# power-supply_combined_v1.net
KiCad netlist of a schematic drawn in EAGLE
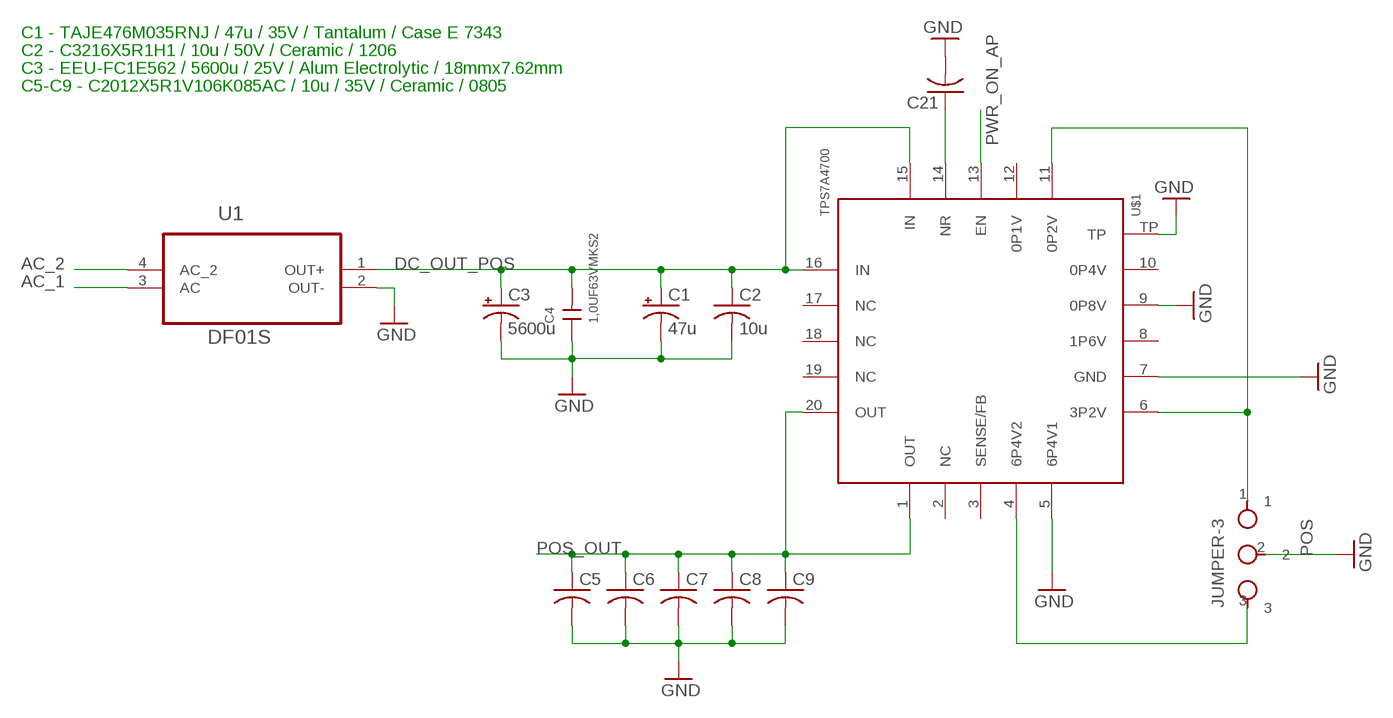
[diagram p0: schematic, sheet 1]
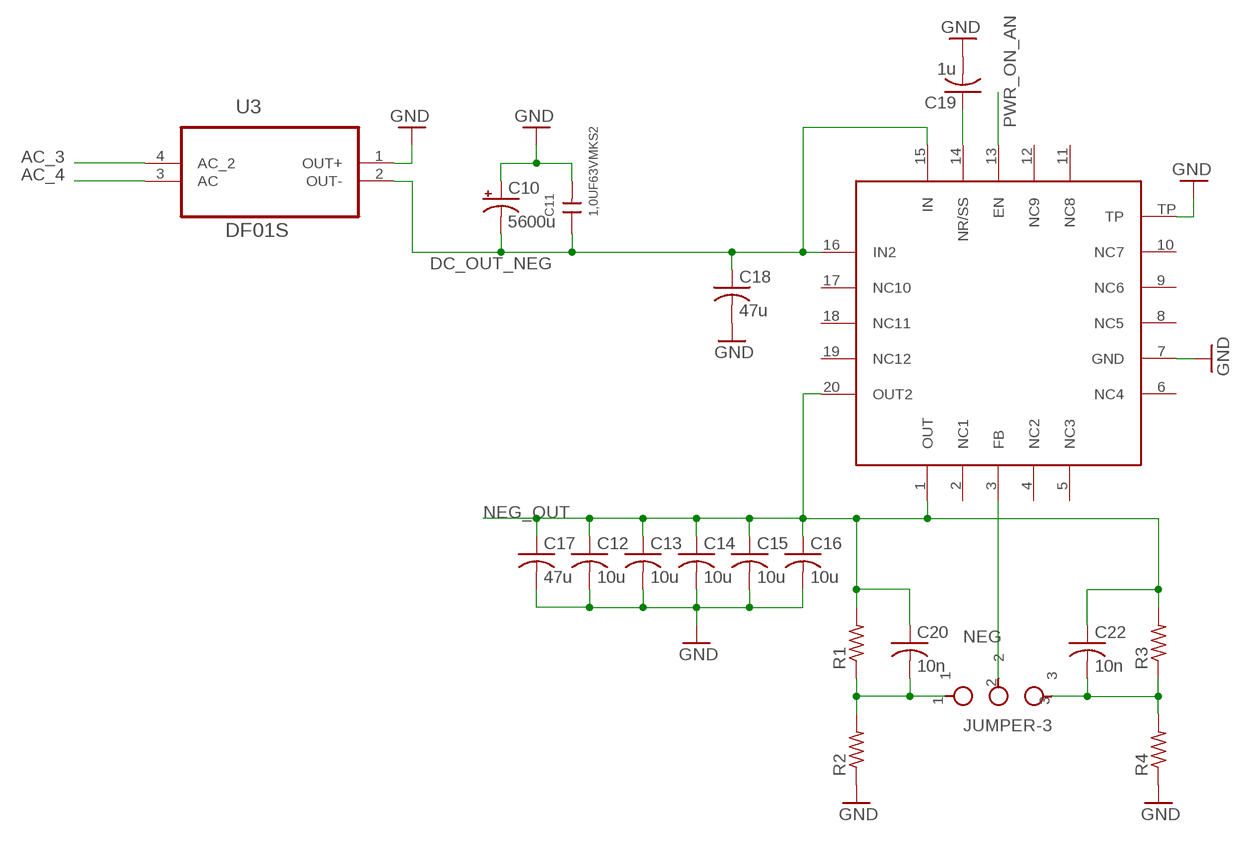
[diagram p1: schematic, sheet 2]
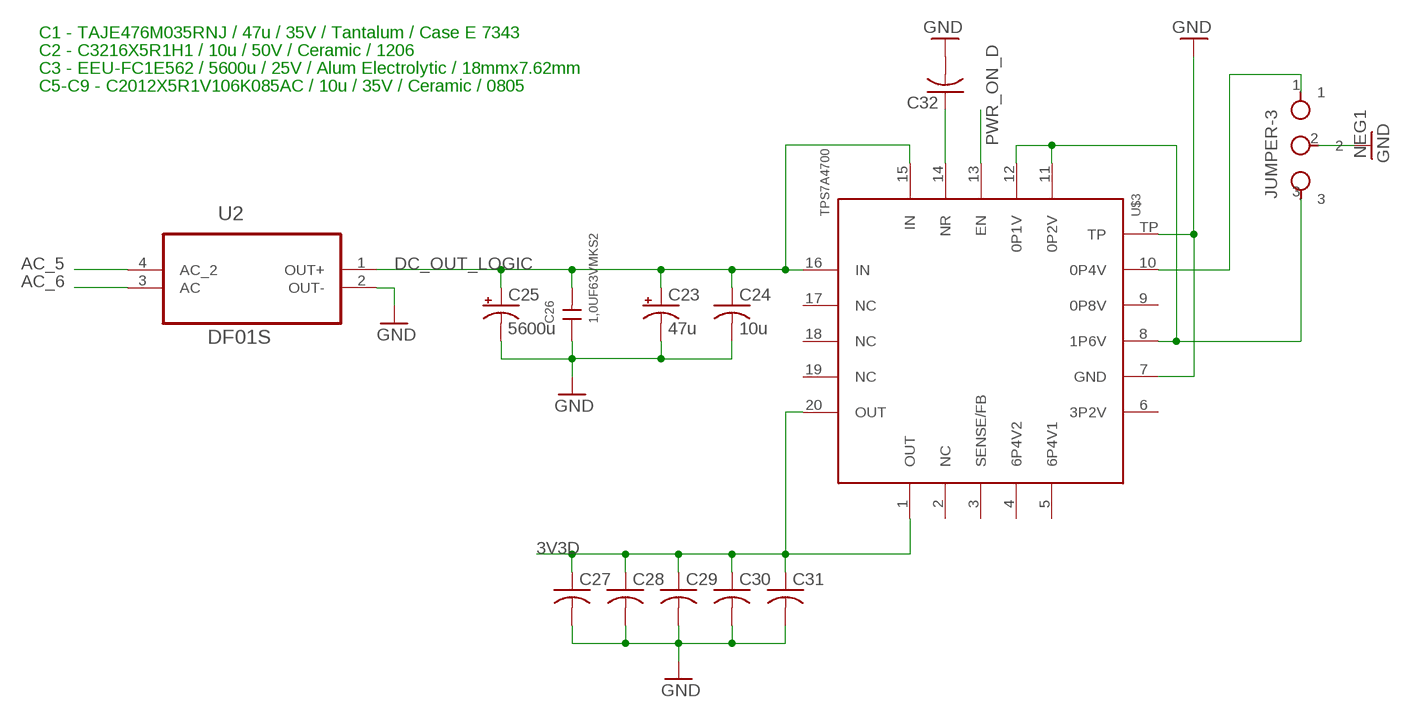
[diagram p2: schematic, sheet 3]
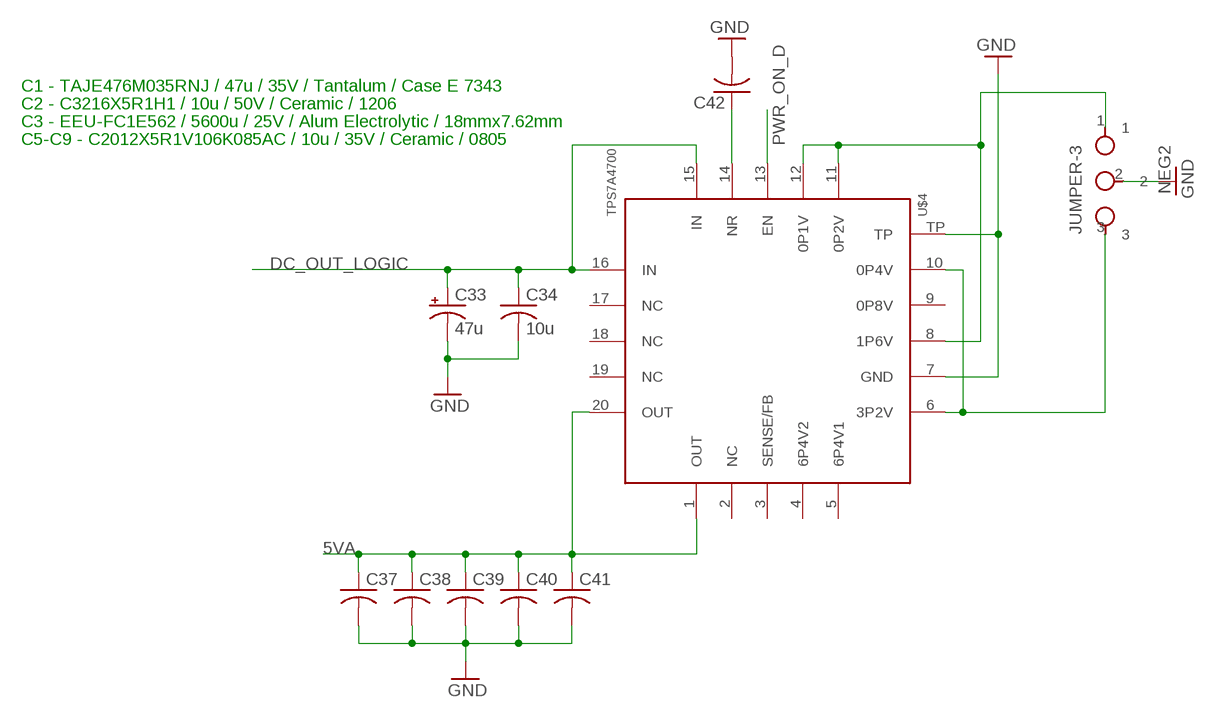
[diagram p3: schematic, sheet 4]
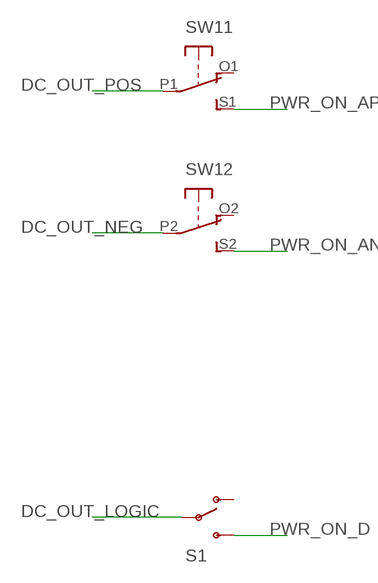
[diagram p4: schematic, sheet 5]

(export (version "E")
  (design (tool "Eeschema 10.0.6"))
  (components
    (comp (ref "S1")
      (value "SWITCH-SPDTSMD")
      (footprint "eagle-import:AYZ0202")
      (libsource (lib "eagle-import") (part "SWITCH-SPDTSMD"))
    )
    (comp (ref "SW1")
      (value "DPDT-EG1390")
      (footprint "eagle-import:EG1390")
      (libsource (lib "eagle-import") (part "DPDT-EG1390"))
    )
    (comp (ref "C33")
      (value "47u")
      (footprint "eagle-import:SMC_E")
      (libsource (lib "eagle-import") (part "CPOL-USSMCE"))
    )
    (comp (ref "C34")
      (value "10u")
      (footprint "eagle-import:C1206")
      (libsource (lib "eagle-import") (part "C-USC1206"))
    )
    (comp (ref "C37")
      (value "C-USC0805")
      (footprint "eagle-import:C0805")
      (libsource (lib "eagle-import") (part "C-USC0805"))
    )
    (comp (ref "C38")
      (value "C-USC0805")
      (footprint "eagle-import:C0805")
      (libsource (lib "eagle-import") (part "C-USC0805"))
    )
    (comp (ref "C39")
      (value "C-USC0805")
      (footprint "eagle-import:C0805")
      (libsource (lib "eagle-import") (part "C-USC0805"))
    )
    (comp (ref "C40")
      (value "C-USC0805")
      (footprint "eagle-import:C0805")
      (libsource (lib "eagle-import") (part "C-USC0805"))
    )
    (comp (ref "C41")
      (value "C-USC0805")
      (footprint "eagle-import:C0805")
      (libsource (lib "eagle-import") (part "C-USC0805"))
    )
    (comp (ref "C42")
      (value "C-USC0603")
      (footprint "eagle-import:C0603")
      (libsource (lib "eagle-import") (part "C-USC0603"))
    )
    (comp (ref "NEG2")
      (value "JUMPER-3")
      (footprint "eagle-import:1X03")
      (libsource (lib "eagle-import") (part "JUMPER-3"))
    )
    (comp (ref "U$4")
      (value "TPS7A4700")
      (footprint "eagle-import:VQFN-20")
      (libsource (lib "eagle-import") (part "TPS7A4700"))
    )
    (comp (ref "C23")
      (value "47u")
      (footprint "eagle-import:SMC_E")
      (libsource (lib "eagle-import") (part "CPOL-USSMCE"))
    )
    (comp (ref "C24")
      (value "10u")
      (footprint "eagle-import:C1206")
      (libsource (lib "eagle-import") (part "C-USC1206"))
    )
    (comp (ref "C25")
      (value "5600u")
      (footprint "eagle-import:E7,5-18")
      (libsource (lib "eagle-import") (part "CPOL-USE7.5-18"))
    )
    (comp (ref "C26")
      (value "1,0UF63VMKS2")
      (footprint "eagle-import:5,0X10,0RM5,0")
      (libsource (lib "eagle-import") (part "1,0UF63VMKS2"))
    )
    (comp (ref "C27")
      (value "C-USC0805")
      (footprint "eagle-import:C0805")
      (libsource (lib "eagle-import") (part "C-USC0805"))
    )
    (comp (ref "C28")
      (value "C-USC0805")
      (footprint "eagle-import:C0805")
      (libsource (lib "eagle-import") (part "C-USC0805"))
    )
    (comp (ref "C29")
      (value "C-USC0805")
      (footprint "eagle-import:C0805")
      (libsource (lib "eagle-import") (part "C-USC0805"))
    )
    (comp (ref "C30")
      (value "C-USC0805")
      (footprint "eagle-import:C0805")
      (libsource (lib "eagle-import") (part "C-USC0805"))
    )
    (comp (ref "C31")
      (value "C-USC0805")
      (footprint "eagle-import:C0805")
      (libsource (lib "eagle-import") (part "C-USC0805"))
    )
    (comp (ref "C32")
      (value "C-USC0603")
      (footprint "eagle-import:C0603")
      (libsource (lib "eagle-import") (part "C-USC0603"))
    )
    (comp (ref "NEG1")
      (value "JUMPER-3")
      (footprint "eagle-import:1X03")
      (libsource (lib "eagle-import") (part "JUMPER-3"))
    )
    (comp (ref "U$3")
      (value "TPS7A4700")
      (footprint "eagle-import:VQFN-20")
      (libsource (lib "eagle-import") (part "TPS7A4700"))
    )
    (comp (ref "U2")
      (value "DF01S")
      (footprint "eagle-import:SOT508P985X260-4N")
      (libsource (lib "eagle-import") (part "DF01S"))
    )
    (comp (ref "C1")
      (value "47u")
      (footprint "eagle-import:SMC_E")
      (libsource (lib "eagle-import") (part "CPOL-USSMCE"))
    )
    (comp (ref "C2")
      (value "10u")
      (footprint "eagle-import:C1206")
      (libsource (lib "eagle-import") (part "C-USC1206"))
    )
    (comp (ref "C3")
      (value "5600u")
      (footprint "eagle-import:E7,5-18")
      (libsource (lib "eagle-import") (part "CPOL-USE7.5-18"))
    )
    (comp (ref "C4")
      (value "1,0UF63VMKS2")
      (footprint "eagle-import:5,0X10,0RM5,0")
      (libsource (lib "eagle-import") (part "1,0UF63VMKS2"))
    )
    (comp (ref "C5")
      (value "C-USC0805")
      (footprint "eagle-import:C0805")
      (libsource (lib "eagle-import") (part "C-USC0805"))
    )
    (comp (ref "C6")
      (value "C-USC0805")
      (footprint "eagle-import:C0805")
      (libsource (lib "eagle-import") (part "C-USC0805"))
    )
    (comp (ref "C7")
      (value "C-USC0805")
      (footprint "eagle-import:C0805")
      (libsource (lib "eagle-import") (part "C-USC0805"))
    )
    (comp (ref "C8")
      (value "C-USC0805")
      (footprint "eagle-import:C0805")
      (libsource (lib "eagle-import") (part "C-USC0805"))
    )
    (comp (ref "C9")
      (value "C-USC0805")
      (footprint "eagle-import:C0805")
      (libsource (lib "eagle-import") (part "C-USC0805"))
    )
    (comp (ref "C21")
      (value "C-USC0603")
      (footprint "eagle-import:C0603")
      (libsource (lib "eagle-import") (part "C-USC0603"))
    )
    (comp (ref "POS")
      (value "JUMPER-3")
      (footprint "eagle-import:1X03")
      (libsource (lib "eagle-import") (part "JUMPER-3"))
    )
    (comp (ref "U$1")
      (value "TPS7A4700")
      (footprint "eagle-import:VQFN-20")
      (libsource (lib "eagle-import") (part "TPS7A4700"))
    )
    (comp (ref "U1")
      (value "DF01S")
      (footprint "eagle-import:SOT508P985X260-4N")
      (libsource (lib "eagle-import") (part "DF01S"))
    )
    (comp (ref "C10")
      (value "5600u")
      (footprint "eagle-import:E7,5-18")
      (libsource (lib "eagle-import") (part "CPOL-USE7.5-18"))
    )
    (comp (ref "C11")
      (value "1,0UF63VMKS2")
      (footprint "eagle-import:5,0X10,0RM5,0")
      (libsource (lib "eagle-import") (part "1,0UF63VMKS2"))
    )
    (comp (ref "C12")
      (value "10u")
      (footprint "eagle-import:C0805")
      (libsource (lib "eagle-import") (part "C-USC0805"))
    )
    (comp (ref "C13")
      (value "10u")
      (footprint "eagle-import:C0805")
      (libsource (lib "eagle-import") (part "C-USC0805"))
    )
    (comp (ref "C14")
      (value "10u")
      (footprint "eagle-import:C0805")
      (libsource (lib "eagle-import") (part "C-USC0805"))
    )
    (comp (ref "C15")
      (value "10u")
      (footprint "eagle-import:C0805")
      (libsource (lib "eagle-import") (part "C-USC0805"))
    )
    (comp (ref "C16")
      (value "10u")
      (footprint "eagle-import:C0805")
      (libsource (lib "eagle-import") (part "C-USC0805"))
    )
    (comp (ref "C17")
      (value "47u")
      (footprint "eagle-import:C2220K")
      (libsource (lib "eagle-import") (part "C-USC2220K"))
    )
    (comp (ref "C18")
      (value "47u")
      (footprint "eagle-import:C2220K")
      (libsource (lib "eagle-import") (part "C-USC2220K"))
    )
    (comp (ref "C19")
      (value "1u")
      (footprint "eagle-import:C0603")
      (libsource (lib "eagle-import") (part "C-USC0603"))
    )
    (comp (ref "C20")
      (value "10n")
      (footprint "eagle-import:C0603")
      (libsource (lib "eagle-import") (part "C-USC0603"))
    )
    (comp (ref "C22")
      (value "10n")
      (footprint "eagle-import:C0603")
      (libsource (lib "eagle-import") (part "C-USC0603"))
    )
    (comp (ref "NEG")
      (value "JUMPER-3")
      (footprint "eagle-import:1X03")
      (libsource (lib "eagle-import") (part "JUMPER-3"))
    )
    (comp (ref "R1")
      (value "R-US_R0603")
      (footprint "eagle-import:R0603")
      (libsource (lib "eagle-import") (part "R-US_R0603"))
    )
    (comp (ref "R2")
      (value "R-US_R0603")
      (footprint "eagle-import:R0603")
      (libsource (lib "eagle-import") (part "R-US_R0603"))
    )
    (comp (ref "R3")
      (value "R-US_R0603")
      (footprint "eagle-import:R0603")
      (libsource (lib "eagle-import") (part "R-US_R0603"))
    )
    (comp (ref "R4")
      (value "R-US_R0603")
      (footprint "eagle-import:R0603")
      (libsource (lib "eagle-import") (part "R-US_R0603"))
    )
    (comp (ref "U$2")
      (value "TPS7A3301RGWT")
      (footprint "eagle-import:VQFN-20")
      (libsource (lib "eagle-import") (part "TPS7A3301RGWT"))
    )
    (comp (ref "U3")
      (value "DF01S")
      (footprint "eagle-import:SOT508P985X260-4N")
      (libsource (lib "eagle-import") (part "DF01S"))
    )
  )
  (nets
    (net (code "1") (name "3V3D") (class "Default")
      (node (ref "C27") (pin "1") (pinfunction "1_1") (pintype "passive"))
      (node (ref "C28") (pin "1") (pinfunction "1_1") (pintype "passive"))
      (node (ref "C29") (pin "1") (pinfunction "1_1") (pintype "passive"))
      (node (ref "C30") (pin "1") (pinfunction "1_1") (pintype "passive"))
      (node (ref "C31") (pin "1") (pinfunction "1_1") (pintype "passive"))
      (node (ref "U$3") (pin "1") (pinfunction "OUT_1") (pintype "bidirectional"))
      (node (ref "U$3") (pin "20") (pinfunction "OUT_20") (pintype "bidirectional"))
    )
    (net (code "2") (name "5VA") (class "Default")
      (node (ref "C37") (pin "1") (pinfunction "1_1") (pintype "passive"))
      (node (ref "C38") (pin "1") (pinfunction "1_1") (pintype "passive"))
      (node (ref "C39") (pin "1") (pinfunction "1_1") (pintype "passive"))
      (node (ref "C40") (pin "1") (pinfunction "1_1") (pintype "passive"))
      (node (ref "C41") (pin "1") (pinfunction "1_1") (pintype "passive"))
      (node (ref "U$4") (pin "1") (pinfunction "OUT_1") (pintype "bidirectional"))
      (node (ref "U$4") (pin "20") (pinfunction "OUT_20") (pintype "bidirectional"))
    )
    (net (code "3") (name "AC_1") (class "Default")
      (node (ref "U1") (pin "3") (pinfunction "AC_3") (pintype "input"))
    )
    (net (code "4") (name "AC_2") (class "Default")
      (node (ref "U1") (pin "4") (pinfunction "AC_2_4") (pintype "input"))
    )
    (net (code "5") (name "AC_3") (class "Default")
      (node (ref "U3") (pin "4") (pinfunction "AC_2_4") (pintype "input"))
    )
    (net (code "6") (name "AC_4") (class "Default")
      (node (ref "U3") (pin "3") (pinfunction "AC_3") (pintype "input"))
    )
    (net (code "7") (name "AC_5") (class "Default")
      (node (ref "U2") (pin "4") (pinfunction "AC_2_4") (pintype "input"))
    )
    (net (code "8") (name "AC_6") (class "Default")
      (node (ref "U2") (pin "3") (pinfunction "AC_3") (pintype "input"))
    )
    (net (code "9") (name "DC_OUT_LOGIC") (class "Default")
      (node (ref "C23") (pin "+") (pinfunction "+_+") (pintype "passive"))
      (node (ref "C24") (pin "1") (pinfunction "1_1") (pintype "passive"))
      (node (ref "C25") (pin "+") (pinfunction "+_+") (pintype "passive"))
      (node (ref "C26") (pin "2") (pinfunction "2_2") (pintype "passive"))
      (node (ref "C33") (pin "+") (pinfunction "+_+") (pintype "passive"))
      (node (ref "C34") (pin "1") (pinfunction "1_1") (pintype "passive"))
      (node (ref "S1") (pin "2") (pinfunction "P_2") (pintype "passive"))
      (node (ref "U$3") (pin "15") (pinfunction "IN_15") (pintype "bidirectional"))
      (node (ref "U$3") (pin "16") (pinfunction "IN_16") (pintype "bidirectional"))
      (node (ref "U$4") (pin "15") (pinfunction "IN_15") (pintype "bidirectional"))
      (node (ref "U$4") (pin "16") (pinfunction "IN_16") (pintype "bidirectional"))
      (node (ref "U2") (pin "1") (pinfunction "OUT+_1") (pintype "output"))
    )
    (net (code "10") (name "DC_OUT_NEG") (class "Default")
      (node (ref "C10") (pin "-") (pinfunction "-_-") (pintype "passive"))
      (node (ref "C11") (pin "1") (pinfunction "1_1") (pintype "passive"))
      (node (ref "C18") (pin "1") (pinfunction "1_1") (pintype "passive"))
      (node (ref "SW1") (pin "P2") (pinfunction "P_P2") (pintype "passive"))
      (node (ref "U$2") (pin "15") (pinfunction "IN_15") (pintype "bidirectional"))
      (node (ref "U$2") (pin "16") (pinfunction "IN2_16") (pintype "bidirectional"))
      (node (ref "U3") (pin "2") (pinfunction "OUT-_2") (pintype "output"))
    )
    (net (code "11") (name "DC_OUT_POS") (class "Default")
      (node (ref "C1") (pin "+") (pinfunction "+_+") (pintype "passive"))
      (node (ref "C2") (pin "1") (pinfunction "1_1") (pintype "passive"))
      (node (ref "C3") (pin "+") (pinfunction "+_+") (pintype "passive"))
      (node (ref "C4") (pin "2") (pinfunction "2_2") (pintype "passive"))
      (node (ref "SW1") (pin "P1") (pinfunction "P_P1") (pintype "passive"))
      (node (ref "U$1") (pin "15") (pinfunction "IN_15") (pintype "bidirectional"))
      (node (ref "U$1") (pin "16") (pinfunction "IN_16") (pintype "bidirectional"))
      (node (ref "U1") (pin "1") (pinfunction "OUT+_1") (pintype "output"))
    )
    (net (code "12") (name "GND") (class "Default")
      (node (ref "C1") (pin "-") (pinfunction "-_-") (pintype "passive"))
      (node (ref "C10") (pin "+") (pinfunction "+_+") (pintype "passive"))
      (node (ref "C11") (pin "2") (pinfunction "2_2") (pintype "passive"))
      (node (ref "C12") (pin "2") (pinfunction "2_2") (pintype "passive"))
      (node (ref "C13") (pin "2") (pinfunction "2_2") (pintype "passive"))
      (node (ref "C14") (pin "2") (pinfunction "2_2") (pintype "passive"))
      (node (ref "C15") (pin "2") (pinfunction "2_2") (pintype "passive"))
      (node (ref "C16") (pin "2") (pinfunction "2_2") (pintype "passive"))
      (node (ref "C17") (pin "2") (pinfunction "2_2") (pintype "passive"))
      (node (ref "C18") (pin "2") (pinfunction "2_2") (pintype "passive"))
      (node (ref "C19") (pin "2") (pinfunction "2_2") (pintype "passive"))
      (node (ref "C2") (pin "2") (pinfunction "2_2") (pintype "passive"))
      (node (ref "C21") (pin "2") (pinfunction "2_2") (pintype "passive"))
      (node (ref "C23") (pin "-") (pinfunction "-_-") (pintype "passive"))
      (node (ref "C24") (pin "2") (pinfunction "2_2") (pintype "passive"))
      (node (ref "C25") (pin "-") (pinfunction "-_-") (pintype "passive"))
      (node (ref "C26") (pin "1") (pinfunction "1_1") (pintype "passive"))
      (node (ref "C27") (pin "2") (pinfunction "2_2") (pintype "passive"))
      (node (ref "C28") (pin "2") (pinfunction "2_2") (pintype "passive"))
      (node (ref "C29") (pin "2") (pinfunction "2_2") (pintype "passive"))
      (node (ref "C3") (pin "-") (pinfunction "-_-") (pintype "passive"))
      (node (ref "C30") (pin "2") (pinfunction "2_2") (pintype "passive"))
      (node (ref "C31") (pin "2") (pinfunction "2_2") (pintype "passive"))
      (node (ref "C32") (pin "2") (pinfunction "2_2") (pintype "passive"))
      (node (ref "C33") (pin "-") (pinfunction "-_-") (pintype "passive"))
      (node (ref "C34") (pin "2") (pinfunction "2_2") (pintype "passive"))
      (node (ref "C37") (pin "2") (pinfunction "2_2") (pintype "passive"))
      (node (ref "C38") (pin "2") (pinfunction "2_2") (pintype "passive"))
      (node (ref "C39") (pin "2") (pinfunction "2_2") (pintype "passive"))
      (node (ref "C4") (pin "1") (pinfunction "1_1") (pintype "passive"))
      (node (ref "C40") (pin "2") (pinfunction "2_2") (pintype "passive"))
      (node (ref "C41") (pin "2") (pinfunction "2_2") (pintype "passive"))
      (node (ref "C42") (pin "2") (pinfunction "2_2") (pintype "passive"))
      (node (ref "C5") (pin "2") (pinfunction "2_2") (pintype "passive"))
      (node (ref "C6") (pin "2") (pinfunction "2_2") (pintype "passive"))
      (node (ref "C7") (pin "2") (pinfunction "2_2") (pintype "passive"))
      (node (ref "C8") (pin "2") (pinfunction "2_2") (pintype "passive"))
      (node (ref "C9") (pin "2") (pinfunction "2_2") (pintype "passive"))
      (node (ref "NEG1") (pin "2") (pinfunction "2_2") (pintype "bidirectional"))
      (node (ref "NEG2") (pin "2") (pinfunction "2_2") (pintype "bidirectional"))
      (node (ref "POS") (pin "2") (pinfunction "2_2") (pintype "bidirectional"))
      (node (ref "R2") (pin "1") (pinfunction "1_1") (pintype "passive"))
      (node (ref "R4") (pin "1") (pinfunction "1_1") (pintype "passive"))
      (node (ref "U$1") (pin "5") (pinfunction "6P4V1_5") (pintype "bidirectional"))
      (node (ref "U$1") (pin "7") (pinfunction "GND_7") (pintype "bidirectional"))
      (node (ref "U$1") (pin "9") (pinfunction "0P8V_9") (pintype "bidirectional"))
      (node (ref "U$1") (pin "TP") (pinfunction "TP_TP") (pintype "bidirectional"))
      (node (ref "U$2") (pin "7") (pinfunction "GND_7") (pintype "bidirectional"))
      (node (ref "U$2") (pin "TP") (pinfunction "TP_TP") (pintype "bidirectional"))
      (node (ref "U$3") (pin "7") (pinfunction "GND_7") (pintype "bidirectional"))
      (node (ref "U$3") (pin "TP") (pinfunction "TP_TP") (pintype "bidirectional"))
      (node (ref "U$4") (pin "7") (pinfunction "GND_7") (pintype "bidirectional"))
      (node (ref "U$4") (pin "TP") (pinfunction "TP_TP") (pintype "bidirectional"))
      (node (ref "U1") (pin "2") (pinfunction "OUT-_2") (pintype "output"))
      (node (ref "U2") (pin "2") (pinfunction "OUT-_2") (pintype "output"))
      (node (ref "U3") (pin "1") (pinfunction "OUT+_1") (pintype "output"))
    )
    (net (code "13") (name "NEG_OUT") (class "Default")
      (node (ref "C12") (pin "1") (pinfunction "1_1") (pintype "passive"))
      (node (ref "C13") (pin "1") (pinfunction "1_1") (pintype "passive"))
      (node (ref "C14") (pin "1") (pinfunction "1_1") (pintype "passive"))
      (node (ref "C15") (pin "1") (pinfunction "1_1") (pintype "passive"))
      (node (ref "C16") (pin "1") (pinfunction "1_1") (pintype "passive"))
      (node (ref "C17") (pin "1") (pinfunction "1_1") (pintype "passive"))
      (node (ref "C20") (pin "1") (pinfunction "1_1") (pintype "passive"))
      (node (ref "C22") (pin "1") (pinfunction "1_1") (pintype "passive"))
      (node (ref "R1") (pin "2") (pinfunction "2_2") (pintype "passive"))
      (node (ref "R3") (pin "2") (pinfunction "2_2") (pintype "passive"))
      (node (ref "U$2") (pin "1") (pinfunction "OUT_1") (pintype "bidirectional"))
      (node (ref "U$2") (pin "20") (pinfunction "OUT2_20") (pintype "bidirectional"))
    )
    (net (code "14") (name "Net-(C20-Pad2)") (class "Default")
      (node (ref "C20") (pin "2") (pinfunction "2_2") (pintype "passive"))
      (node (ref "NEG") (pin "1") (pinfunction "1_1") (pintype "bidirectional"))
      (node (ref "R1") (pin "1") (pinfunction "1_1") (pintype "passive"))
      (node (ref "R2") (pin "2") (pinfunction "2_2") (pintype "passive"))
    )
    (net (code "15") (name "Net-(C22-Pad2)") (class "Default")
      (node (ref "C22") (pin "2") (pinfunction "2_2") (pintype "passive"))
      (node (ref "NEG") (pin "3") (pinfunction "3_3") (pintype "bidirectional"))
      (node (ref "R3") (pin "1") (pinfunction "1_1") (pintype "passive"))
      (node (ref "R4") (pin "2") (pinfunction "2_2") (pintype "passive"))
    )
    (net (code "16") (name "Net-(U$1-0P2V)") (class "Default")
      (node (ref "POS") (pin "1") (pinfunction "1_1") (pintype "bidirectional"))
      (node (ref "U$1") (pin "11") (pinfunction "0P2V_11") (pintype "bidirectional"))
      (node (ref "U$1") (pin "6") (pinfunction "3P2V_6") (pintype "bidirectional"))
    )
    (net (code "17") (name "Net-(U$1-6P4V2)") (class "Default")
      (node (ref "POS") (pin "3") (pinfunction "3_3") (pintype "bidirectional"))
      (node (ref "U$1") (pin "4") (pinfunction "6P4V2_4") (pintype "bidirectional"))
    )
    (net (code "18") (name "Net-(U$1-NR)") (class "Default")
      (node (ref "C21") (pin "1") (pinfunction "1_1") (pintype "passive"))
      (node (ref "U$1") (pin "14") (pinfunction "NR_14") (pintype "bidirectional"))
    )
    (net (code "19") (name "Net-(U$2-FB)") (class "Default")
      (node (ref "NEG") (pin "2") (pinfunction "2_2") (pintype "bidirectional"))
      (node (ref "U$2") (pin "3") (pinfunction "FB_3") (pintype "bidirectional"))
    )
    (net (code "20") (name "Net-(U$2-NR{slash}SS)") (class "Default")
      (node (ref "C19") (pin "1") (pinfunction "1_1") (pintype "passive"))
      (node (ref "U$2") (pin "14") (pinfunction "NR/SS_14") (pintype "bidirectional"))
    )
    (net (code "21") (name "Net-(U$3-0P1V)") (class "Default")
      (node (ref "NEG1") (pin "3") (pinfunction "3_3") (pintype "bidirectional"))
      (node (ref "U$3") (pin "11") (pinfunction "0P2V_11") (pintype "bidirectional"))
      (node (ref "U$3") (pin "12") (pinfunction "0P1V_12") (pintype "bidirectional"))
      (node (ref "U$3") (pin "8") (pinfunction "1P6V_8") (pintype "bidirectional"))
    )
    (net (code "22") (name "Net-(U$3-0P4V)") (class "Default")
      (node (ref "NEG1") (pin "1") (pinfunction "1_1") (pintype "bidirectional"))
      (node (ref "U$3") (pin "10") (pinfunction "0P4V_10") (pintype "bidirectional"))
    )
    (net (code "23") (name "Net-(U$3-NR)") (class "Default")
      (node (ref "C32") (pin "1") (pinfunction "1_1") (pintype "passive"))
      (node (ref "U$3") (pin "14") (pinfunction "NR_14") (pintype "bidirectional"))
    )
    (net (code "24") (name "Net-(U$4-0P1V)") (class "Default")
      (node (ref "NEG2") (pin "1") (pinfunction "1_1") (pintype "bidirectional"))
      (node (ref "U$4") (pin "11") (pinfunction "0P2V_11") (pintype "bidirectional"))
      (node (ref "U$4") (pin "12") (pinfunction "0P1V_12") (pintype "bidirectional"))
      (node (ref "U$4") (pin "8") (pinfunction "1P6V_8") (pintype "bidirectional"))
    )
    (net (code "25") (name "Net-(U$4-0P4V)") (class "Default")
      (node (ref "NEG2") (pin "3") (pinfunction "3_3") (pintype "bidirectional"))
      (node (ref "U$4") (pin "10") (pinfunction "0P4V_10") (pintype "bidirectional"))
      (node (ref "U$4") (pin "6") (pinfunction "3P2V_6") (pintype "bidirectional"))
    )
    (net (code "26") (name "Net-(U$4-NR)") (class "Default")
      (node (ref "C42") (pin "1") (pinfunction "1_1") (pintype "passive"))
      (node (ref "U$4") (pin "14") (pinfunction "NR_14") (pintype "bidirectional"))
    )
    (net (code "27") (name "POS_OUT") (class "Default")
      (node (ref "C5") (pin "1") (pinfunction "1_1") (pintype "passive"))
      (node (ref "C6") (pin "1") (pinfunction "1_1") (pintype "passive"))
      (node (ref "C7") (pin "1") (pinfunction "1_1") (pintype "passive"))
      (node (ref "C8") (pin "1") (pinfunction "1_1") (pintype "passive"))
      (node (ref "C9") (pin "1") (pinfunction "1_1") (pintype "passive"))
      (node (ref "U$1") (pin "1") (pinfunction "OUT_1") (pintype "bidirectional"))
      (node (ref "U$1") (pin "20") (pinfunction "OUT_20") (pintype "bidirectional"))
    )
    (net (code "28") (name "PWR_ON_AN") (class "Default")
      (node (ref "SW1") (pin "S2") (pinfunction "S_S2") (pintype "passive"))
      (node (ref "U$2") (pin "13") (pinfunction "EN_13") (pintype "bidirectional"))
    )
    (net (code "29") (name "PWR_ON_AP") (class "Default")
      (node (ref "SW1") (pin "S1") (pinfunction "S_S1") (pintype "passive"))
      (node (ref "U$1") (pin "13") (pinfunction "EN_13") (pintype "bidirectional"))
    )
    (net (code "30") (name "PWR_ON_D") (class "Default")
      (node (ref "S1") (pin "3") (pinfunction "S_3") (pintype "passive"))
      (node (ref "U$3") (pin "13") (pinfunction "EN_13") (pintype "bidirectional"))
      (node (ref "U$4") (pin "13") (pinfunction "EN_13") (pintype "bidirectional"))
    )
    (net (code "31") (name "unconnected-(S1-O-Pad1)") (class "Default")
      (node (ref "S1") (pin "1") (pinfunction "O_1") (pintype "passive"))
    )
    (net (code "32") (name "unconnected-(SW1A-O-PadO1)") (class "Default")
      (node (ref "SW1") (pin "O1") (pinfunction "O_O1") (pintype "passive"))
    )
    (net (code "33") (name "unconnected-(SW1B-O-PadO2)") (class "Default")
      (node (ref "SW1") (pin "O2") (pinfunction "O_O2") (pintype "passive"))
    )
    (net (code "34") (name "unconnected-(U$1-0P1V-Pad12)") (class "Default")
      (node (ref "U$1") (pin "12") (pinfunction "0P1V_12") (pintype "bidirectional"))
    )
    (net (code "35") (name "unconnected-(U$1-0P4V-Pad10)") (class "Default")
      (node (ref "U$1") (pin "10") (pinfunction "0P4V_10") (pintype "bidirectional"))
    )
    (net (code "36") (name "unconnected-(U$1-1P6V-Pad8)") (class "Default")
      (node (ref "U$1") (pin "8") (pinfunction "1P6V_8") (pintype "bidirectional"))
    )
    (net (code "37") (name "unconnected-(U$1-NC-Pad2)") (class "Default")
      (node (ref "U$1") (pin "2") (pinfunction "NC_2") (pintype "bidirectional"))
    )
    (net (code "38") (name "unconnected-(U$1-NC-Pad17)") (class "Default")
      (node (ref "U$1") (pin "17") (pinfunction "NC_17") (pintype "bidirectional"))
    )
    (net (code "39") (name "unconnected-(U$1-NC-Pad18)") (class "Default")
      (node (ref "U$1") (pin "18") (pinfunction "NC_18") (pintype "bidirectional"))
    )
    (net (code "40") (name "unconnected-(U$1-NC-Pad19)") (class "Default")
      (node (ref "U$1") (pin "19") (pinfunction "NC_19") (pintype "bidirectional"))
    )
    (net (code "41") (name "unconnected-(U$1-SENSE{slash}FB-Pad3)") (class "Default")
      (node (ref "U$1") (pin "3") (pinfunction "SENSE/FB_3") (pintype "bidirectional"))
    )
    (net (code "42") (name "unconnected-(U$2-NC1-Pad2)") (class "Default")
      (node (ref "U$2") (pin "2") (pinfunction "NC1_2") (pintype "bidirectional"))
    )
    (net (code "43") (name "unconnected-(U$2-NC2-Pad4)") (class "Default")
      (node (ref "U$2") (pin "4") (pinfunction "NC2_4") (pintype "bidirectional"))
    )
    (net (code "44") (name "unconnected-(U$2-NC3-Pad5)") (class "Default")
      (node (ref "U$2") (pin "5") (pinfunction "NC3_5") (pintype "bidirectional"))
    )
    (net (code "45") (name "unconnected-(U$2-NC4-Pad6)") (class "Default")
      (node (ref "U$2") (pin "6") (pinfunction "NC4_6") (pintype "bidirectional"))
    )
    (net (code "46") (name "unconnected-(U$2-NC5-Pad8)") (class "Default")
      (node (ref "U$2") (pin "8") (pinfunction "NC5_8") (pintype "bidirectional"))
    )
    (net (code "47") (name "unconnected-(U$2-NC6-Pad9)") (class "Default")
      (node (ref "U$2") (pin "9") (pinfunction "NC6_9") (pintype "bidirectional"))
    )
    (net (code "48") (name "unconnected-(U$2-NC7-Pad10)") (class "Default")
      (node (ref "U$2") (pin "10") (pinfunction "NC7_10") (pintype "bidirectional"))
    )
    (net (code "49") (name "unconnected-(U$2-NC8-Pad11)") (class "Default")
      (node (ref "U$2") (pin "11") (pinfunction "NC8_11") (pintype "bidirectional"))
    )
    (net (code "50") (name "unconnected-(U$2-NC9-Pad12)") (class "Default")
      (node (ref "U$2") (pin "12") (pinfunction "NC9_12") (pintype "bidirectional"))
    )
    (net (code "51") (name "unconnected-(U$2-NC10-Pad17)") (class "Default")
      (node (ref "U$2") (pin "17") (pinfunction "NC10_17") (pintype "bidirectional"))
    )
    (net (code "52") (name "unconnected-(U$2-NC11-Pad18)") (class "Default")
      (node (ref "U$2") (pin "18") (pinfunction "NC11_18") (pintype "bidirectional"))
    )
    (net (code "53") (name "unconnected-(U$2-NC12-Pad19)") (class "Default")
      (node (ref "U$2") (pin "19") (pinfunction "NC12_19") (pintype "bidirectional"))
    )
    (net (code "54") (name "unconnected-(U$3-0P8V-Pad9)") (class "Default")
      (node (ref "U$3") (pin "9") (pinfunction "0P8V_9") (pintype "bidirectional"))
    )
    (net (code "55") (name "unconnected-(U$3-3P2V-Pad6)") (class "Default")
      (node (ref "U$3") (pin "6") (pinfunction "3P2V_6") (pintype "bidirectional"))
    )
    (net (code "56") (name "unconnected-(U$3-6P4V1-Pad5)") (class "Default")
      (node (ref "U$3") (pin "5") (pinfunction "6P4V1_5") (pintype "bidirectional"))
    )
    (net (code "57") (name "unconnected-(U$3-6P4V2-Pad4)") (class "Default")
      (node (ref "U$3") (pin "4") (pinfunction "6P4V2_4") (pintype "bidirectional"))
    )
    (net (code "58") (name "unconnected-(U$3-NC-Pad2)") (class "Default")
      (node (ref "U$3") (pin "2") (pinfunction "NC_2") (pintype "bidirectional"))
    )
    (net (code "59") (name "unconnected-(U$3-NC-Pad17)") (class "Default")
      (node (ref "U$3") (pin "17") (pinfunction "NC_17") (pintype "bidirectional"))
    )
    (net (code "60") (name "unconnected-(U$3-NC-Pad18)") (class "Default")
      (node (ref "U$3") (pin "18") (pinfunction "NC_18") (pintype "bidirectional"))
    )
    (net (code "61") (name "unconnected-(U$3-NC-Pad19)") (class "Default")
      (node (ref "U$3") (pin "19") (pinfunction "NC_19") (pintype "bidirectional"))
    )
    (net (code "62") (name "unconnected-(U$3-SENSE{slash}FB-Pad3)") (class "Default")
      (node (ref "U$3") (pin "3") (pinfunction "SENSE/FB_3") (pintype "bidirectional"))
    )
    (net (code "63") (name "unconnected-(U$4-0P8V-Pad9)") (class "Default")
      (node (ref "U$4") (pin "9") (pinfunction "0P8V_9") (pintype "bidirectional"))
    )
    (net (code "64") (name "unconnected-(U$4-6P4V1-Pad5)") (class "Default")
      (node (ref "U$4") (pin "5") (pinfunction "6P4V1_5") (pintype "bidirectional"))
    )
    (net (code "65") (name "unconnected-(U$4-6P4V2-Pad4)") (class "Default")
      (node (ref "U$4") (pin "4") (pinfunction "6P4V2_4") (pintype "bidirectional"))
    )
    (net (code "66") (name "unconnected-(U$4-NC-Pad2)") (class "Default")
      (node (ref "U$4") (pin "2") (pinfunction "NC_2") (pintype "bidirectional"))
    )
    (net (code "67") (name "unconnected-(U$4-NC-Pad17)") (class "Default")
      (node (ref "U$4") (pin "17") (pinfunction "NC_17") (pintype "bidirectional"))
    )
    (net (code "68") (name "unconnected-(U$4-NC-Pad18)") (class "Default")
      (node (ref "U$4") (pin "18") (pinfunction "NC_18") (pintype "bidirectional"))
    )
    (net (code "69") (name "unconnected-(U$4-NC-Pad19)") (class "Default")
      (node (ref "U$4") (pin "19") (pinfunction "NC_19") (pintype "bidirectional"))
    )
    (net (code "70") (name "unconnected-(U$4-SENSE{slash}FB-Pad3)") (class "Default")
      (node (ref "U$4") (pin "3") (pinfunction "SENSE/FB_3") (pintype "bidirectional"))
    )
  )
)
